# Schematics.net
KiCad netlist of a schematic drawn in Altium Designer
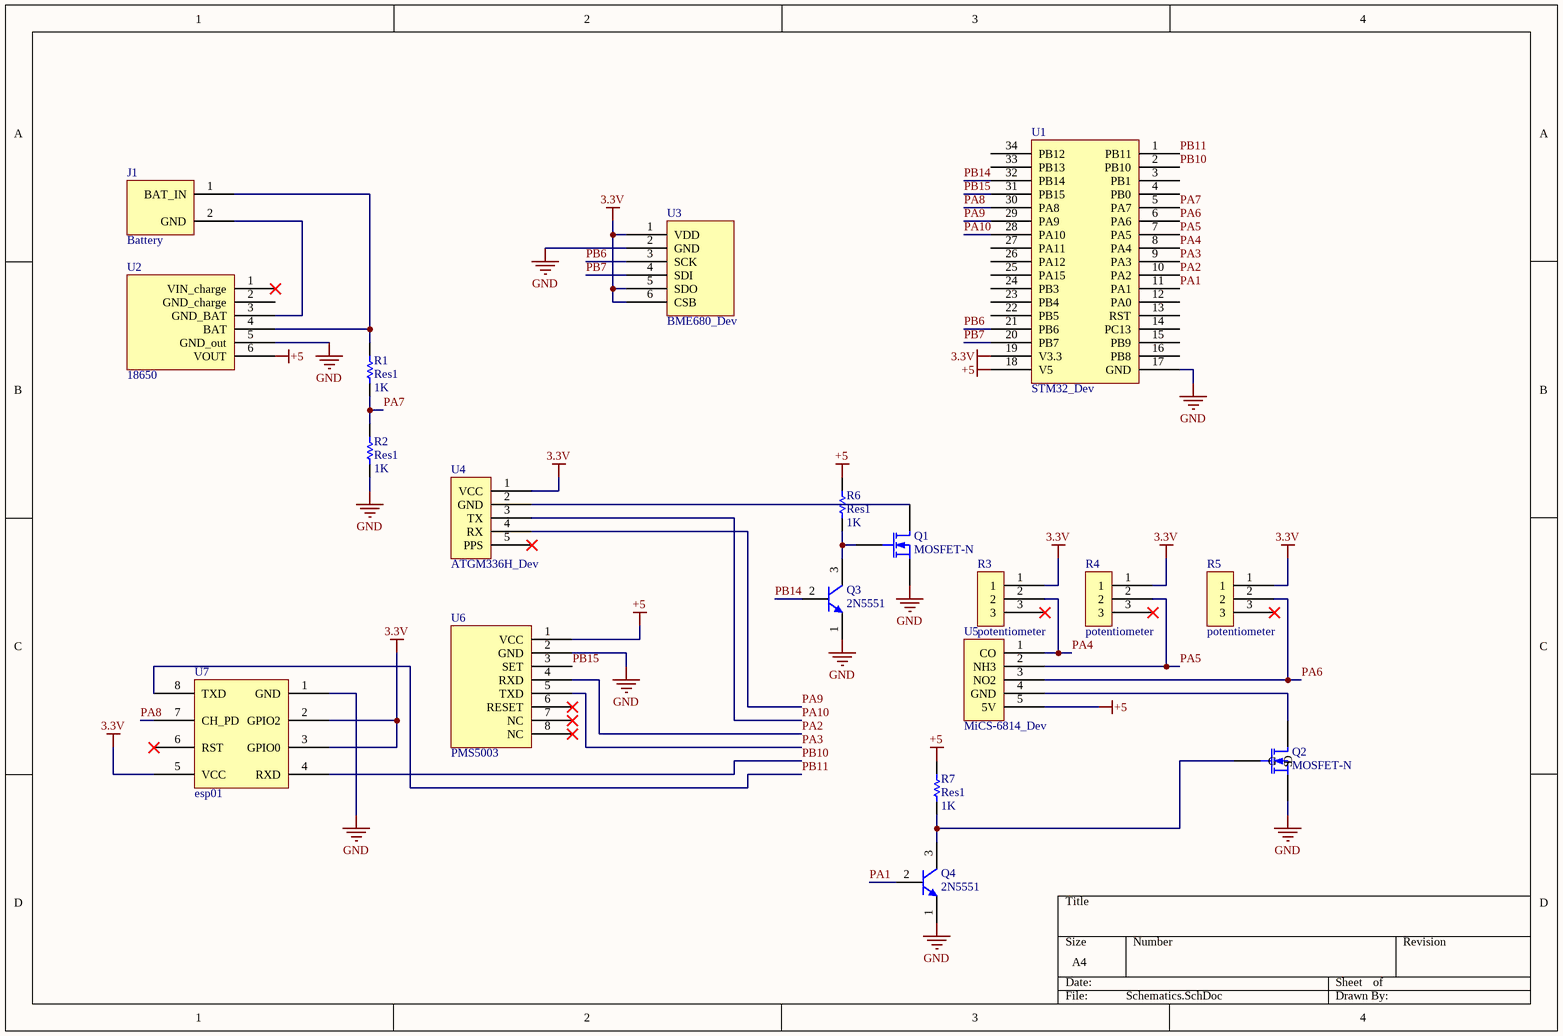
[diagram p0: Schematics.SchDoc]

(export (version "E")
  (design (tool "Eeschema 10.0.6"))
  (components
    (comp (ref "J1") (value "Battery") (footprint "Battery") (libsource (lib "SDLib") (part "Battery")))
    (comp (ref "Q1")
      (value "MOSFET-N")
      (footprint "TO-220-AB")
      (description "N-Channel MOSFET")
      (fields (field (name "PUBLISHER") "Altium Limited"))
      (libsource (lib "Miscellaneous Devices") (part "MOSFET-N"))
    )
    (comp (ref "Q2")
      (value "MOSFET-N")
      (footprint "TO-220-AB")
      (description "N-Channel MOSFET")
      (fields (field (name "PUBLISHER") "Altium Limited"))
      (libsource (lib "") (part "MOSFET-N_1"))
    )
    (comp (ref "Q3")
      (value "2N5551")
      (footprint "TO-92A")
      (description "NPN General Purpose Amplifier")
      (fields (field (name "PUBLISHER") "Altium Limited"))
      (libsource (lib "Miscellaneous Devices") (part "2N3904"))
    )
    (comp (ref "Q4")
      (value "2N5551")
      (footprint "TO-92A")
      (description "NPN General Purpose Amplifier")
      (fields (field (name "PUBLISHER") "Altium Limited"))
      (libsource (lib "Miscellaneous Devices") (part "2N3904"))
    )
    (comp (ref "R1")
      (value "Res1")
      (footprint "AXIAL-0.3")
      (description "Resistor")
      (fields (field (name "ALTIUM_VALUE") "1K") (field (name "PUBLISHER") "Altium Limited"))
      (libsource (lib "Miscellaneous Devices") (part "Res1"))
    )
    (comp (ref "R2")
      (value "Res1")
      (footprint "AXIAL-0.3")
      (description "Resistor")
      (fields (field (name "ALTIUM_VALUE") "1K") (field (name "PUBLISHER") "Altium Limited"))
      (libsource (lib "Miscellaneous Devices") (part "Res1"))
    )
    (comp (ref "R3")
      (value "potentiometer")
      (footprint "potentiometer")
      (libsource (lib "SDLib") (part "potentiometer"))
    )
    (comp (ref "R4")
      (value "potentiometer")
      (footprint "potentiometer")
      (libsource (lib "SDLib") (part "potentiometer"))
    )
    (comp (ref "R5")
      (value "potentiometer")
      (footprint "potentiometer")
      (libsource (lib "SDLib") (part "potentiometer"))
    )
    (comp (ref "R6")
      (value "Res1")
      (footprint "AXIAL-0.3")
      (description "Resistor")
      (fields (field (name "ALTIUM_VALUE") "1K") (field (name "PUBLISHER") "Altium Limited"))
      (libsource (lib "Miscellaneous Devices") (part "Res1"))
    )
    (comp (ref "R7")
      (value "Res1")
      (footprint "AXIAL-0.3")
      (description "Resistor")
      (fields (field (name "ALTIUM_VALUE") "1K") (field (name "PUBLISHER") "Altium Limited"))
      (libsource (lib "Miscellaneous Devices") (part "Res1"))
    )
    (comp (ref "U1") (value "STM32_Dev") (footprint "STM32_Dev") (libsource (lib "SDLib") (part "STM32_Dev")))
    (comp (ref "U2") (value "18650") (footprint "18650_Manage") (libsource (lib "SDLib") (part "18650")))
    (comp (ref "U3")
      (value "BME680_Dev")
      (footprint "BME680_Dev")
      (libsource (lib "SDLib") (part "BME680_Dev"))
    )
    (comp (ref "U4")
      (value "ATGM336H_Dev")
      (footprint "AGTM336H_Dev")
      (libsource (lib "SDLib") (part "ATGM336H_Dev"))
    )
    (comp (ref "U5")
      (value "MiCS-6814_Dev")
      (footprint "MiCS6814")
      (libsource (lib "SDLib") (part "MiCS-6814_Dev"))
    )
    (comp (ref "U6") (value "PMS5003") (footprint "PMS5003") (libsource (lib "SDLib") (part "PMS5003")))
    (comp (ref "U7") (value "esp01") (footprint "ESP01") (libsource (lib "SDLib") (part "esp01")))
  )
  (nets
    (net (code "1") (name "+5") (class "Default")
      (node (ref "R6") (pin "2") (pinfunction "2_2") (pintype "passive"))
      (node (ref "R7") (pin "2") (pinfunction "2_2") (pintype "passive"))
      (node (ref "U1") (pin "18") (pinfunction "V5_18") (pintype "passive"))
      (node (ref "U2") (pin "6") (pinfunction "VOUT_6") (pintype "passive"))
      (node (ref "U5") (pin "5") (pinfunction "5V_5") (pintype "passive"))
      (node (ref "U6") (pin "1") (pinfunction "VCC_1") (pintype "passive"))
    )
    (net (code "2") (name "/PA1") (class "Default")
      (node (ref "Q4") (pin "2") (pinfunction "B_2") (pintype "passive"))
      (node (ref "U1") (pin "11") (pinfunction "PA1_11") (pintype "passive"))
    )
    (net (code "3") (name "/PA2") (class "Default")
      (node (ref "U1") (pin "10") (pinfunction "PA2_10") (pintype "passive"))
      (node (ref "U6") (pin "4") (pinfunction "RXD_4") (pintype "passive"))
    )
    (net (code "4") (name "/PA3") (class "Default")
      (node (ref "U1") (pin "9") (pinfunction "PA3_9") (pintype "passive"))
      (node (ref "U6") (pin "5") (pinfunction "TXD_5") (pintype "passive"))
    )
    (net (code "5") (name "/PA4") (class "Default")
      (node (ref "R3") (pin "2") (pinfunction "2_2") (pintype "passive"))
      (node (ref "U1") (pin "8") (pinfunction "PA4_8") (pintype "passive"))
      (node (ref "U5") (pin "1") (pinfunction "CO_1") (pintype "passive"))
    )
    (net (code "6") (name "/PA5") (class "Default")
      (node (ref "R4") (pin "2") (pinfunction "2_2") (pintype "passive"))
      (node (ref "U1") (pin "7") (pinfunction "PA5_7") (pintype "passive"))
      (node (ref "U5") (pin "2") (pinfunction "NH3_2") (pintype "passive"))
    )
    (net (code "7") (name "/PA6") (class "Default")
      (node (ref "R5") (pin "2") (pinfunction "2_2") (pintype "passive"))
      (node (ref "U1") (pin "6") (pinfunction "PA6_6") (pintype "passive"))
      (node (ref "U5") (pin "3") (pinfunction "NO2_3") (pintype "passive"))
    )
    (net (code "8") (name "/PA7") (class "Default")
      (node (ref "R1") (pin "1") (pinfunction "1_1") (pintype "passive"))
      (node (ref "R2") (pin "2") (pinfunction "2_2") (pintype "passive"))
      (node (ref "U1") (pin "5") (pinfunction "PA7_5") (pintype "passive"))
    )
    (net (code "9") (name "/PA8") (class "Default")
      (node (ref "U1") (pin "30") (pinfunction "PA8_30") (pintype "passive"))
      (node (ref "U7") (pin "7") (pinfunction "CH_PD_7") (pintype "passive"))
    )
    (net (code "10") (name "/PA9") (class "Default")
      (node (ref "U1") (pin "29") (pinfunction "PA9_29") (pintype "passive"))
      (node (ref "U4") (pin "4") (pinfunction "RX_4") (pintype "passive"))
    )
    (net (code "11") (name "/PA10") (class "Default")
      (node (ref "U1") (pin "28") (pinfunction "PA10_28") (pintype "passive"))
      (node (ref "U4") (pin "3") (pinfunction "TX_3") (pintype "passive"))
    )
    (net (code "12") (name "/PB6") (class "Default")
      (node (ref "U1") (pin "21") (pinfunction "PB6_21") (pintype "passive"))
      (node (ref "U3") (pin "3") (pinfunction "SCK_3") (pintype "passive"))
    )
    (net (code "13") (name "/PB7") (class "Default")
      (node (ref "U1") (pin "20") (pinfunction "PB7_20") (pintype "passive"))
      (node (ref "U3") (pin "4") (pinfunction "SDI_4") (pintype "passive"))
    )
    (net (code "14") (name "/PB10") (class "Default")
      (node (ref "U1") (pin "2") (pinfunction "PB10_2") (pintype "passive"))
      (node (ref "U7") (pin "4") (pinfunction "RXD_4") (pintype "passive"))
    )
    (net (code "15") (name "/PB11") (class "Default")
      (node (ref "U1") (pin "1") (pinfunction "PB11_1") (pintype "passive"))
      (node (ref "U7") (pin "8") (pinfunction "TXD_8") (pintype "passive"))
    )
    (net (code "16") (name "/PB14") (class "Default")
      (node (ref "Q3") (pin "2") (pinfunction "B_2") (pintype "passive"))
      (node (ref "U1") (pin "32") (pinfunction "PB14_32") (pintype "passive"))
    )
    (net (code "17") (name "/PB15") (class "Default")
      (node (ref "U1") (pin "31") (pinfunction "PB15_31") (pintype "passive"))
      (node (ref "U6") (pin "3") (pinfunction "SET_3") (pintype "passive"))
    )
    (net (code "18") (name "3.3V") (class "Default")
      (node (ref "R3") (pin "1") (pinfunction "1_1") (pintype "passive"))
      (node (ref "R4") (pin "1") (pinfunction "1_1") (pintype "passive"))
      (node (ref "R5") (pin "1") (pinfunction "1_1") (pintype "passive"))
      (node (ref "U1") (pin "19") (pinfunction "V3.3_19") (pintype "passive"))
      (node (ref "U3") (pin "1") (pinfunction "VDD_1") (pintype "passive"))
      (node (ref "U3") (pin "5") (pinfunction "SDO_5") (pintype "passive"))
      (node (ref "U3") (pin "6") (pinfunction "CSB_6") (pintype "passive"))
      (node (ref "U4") (pin "1") (pinfunction "VCC_1") (pintype "passive"))
      (node (ref "U7") (pin "2") (pinfunction "GPIO2_2") (pintype "passive"))
      (node (ref "U7") (pin "3") (pinfunction "GPIO0_3") (pintype "passive"))
      (node (ref "U7") (pin "5") (pinfunction "VCC_5") (pintype "passive"))
    )
    (net (code "19") (name "GND") (class "Default")
      (node (ref "Q1") (pin "3") (pinfunction "S_3") (pintype "passive"))
      (node (ref "Q2") (pin "3") (pinfunction "S_3") (pintype "passive"))
      (node (ref "Q3") (pin "1") (pinfunction "E_1") (pintype "passive"))
      (node (ref "Q4") (pin "1") (pinfunction "E_1") (pintype "passive"))
      (node (ref "R2") (pin "1") (pinfunction "1_1") (pintype "passive"))
      (node (ref "U1") (pin "17") (pinfunction "GND_17") (pintype "passive"))
      (node (ref "U2") (pin "5") (pinfunction "GND_out_5") (pintype "passive"))
      (node (ref "U3") (pin "2") (pinfunction "GND_2") (pintype "passive"))
      (node (ref "U6") (pin "2") (pinfunction "GND_2") (pintype "passive"))
      (node (ref "U7") (pin "1") (pinfunction "GND_1") (pintype "passive"))
    )
    (net (code "20") (name "Net-(J1-BAT_IN)") (class "Default")
      (node (ref "J1") (pin "1") (pinfunction "BAT_IN_1") (pintype "passive"))
      (node (ref "R1") (pin "2") (pinfunction "2_2") (pintype "passive"))
      (node (ref "U2") (pin "4") (pinfunction "BAT_4") (pintype "passive"))
    )
    (net (code "21") (name "Net-(J1-GND)") (class "Default")
      (node (ref "J1") (pin "2") (pinfunction "GND_2") (pintype "passive"))
      (node (ref "U2") (pin "3") (pinfunction "GND_BAT_3") (pintype "passive"))
    )
    (net (code "22") (name "Net-(Q1-D)") (class "Default")
      (node (ref "Q1") (pin "2") (pinfunction "D_2") (pintype "passive"))
      (node (ref "U4") (pin "2") (pinfunction "GND_2") (pintype "passive"))
    )
    (net (code "23") (name "Net-(Q1-G)") (class "Default")
      (node (ref "Q1") (pin "1") (pinfunction "G_1") (pintype "passive"))
      (node (ref "Q3") (pin "3") (pinfunction "C_3") (pintype "passive"))
      (node (ref "R6") (pin "1") (pinfunction "1_1") (pintype "passive"))
    )
    (net (code "24") (name "Net-(Q2-D)") (class "Default")
      (node (ref "Q2") (pin "2") (pinfunction "D_2") (pintype "passive"))
      (node (ref "U5") (pin "4") (pinfunction "GND_4") (pintype "passive"))
    )
    (net (code "25") (name "Net-(Q2-G)") (class "Default")
      (node (ref "Q2") (pin "1") (pinfunction "G_1") (pintype "passive"))
      (node (ref "Q4") (pin "3") (pinfunction "C_3") (pintype "passive"))
      (node (ref "R7") (pin "1") (pinfunction "1_1") (pintype "passive"))
    )
    (net (code "26") (name "unconnected-(R3-Pad3)") (class "Default")
      (node (ref "R3") (pin "3") (pinfunction "3_3") (pintype "passive+no_connect"))
    )
    (net (code "27") (name "unconnected-(R4-Pad3)") (class "Default")
      (node (ref "R4") (pin "3") (pinfunction "3_3") (pintype "passive+no_connect"))
    )
    (net (code "28") (name "unconnected-(R5-Pad3)") (class "Default")
      (node (ref "R5") (pin "3") (pinfunction "3_3") (pintype "passive+no_connect"))
    )
    (net (code "29") (name "unconnected-(U1-PA0-Pad12)") (class "Default")
      (node (ref "U1") (pin "12") (pinfunction "PA0_12") (pintype "passive"))
    )
    (net (code "30") (name "unconnected-(U1-PA11-Pad27)") (class "Default")
      (node (ref "U1") (pin "27") (pinfunction "PA11_27") (pintype "passive"))
    )
    (net (code "31") (name "unconnected-(U1-PA12-Pad26)") (class "Default")
      (node (ref "U1") (pin "26") (pinfunction "PA12_26") (pintype "passive"))
    )
    (net (code "32") (name "unconnected-(U1-PA15-Pad25)") (class "Default")
      (node (ref "U1") (pin "25") (pinfunction "PA15_25") (pintype "passive"))
    )
    (net (code "33") (name "unconnected-(U1-PB0-Pad4)") (class "Default")
      (node (ref "U1") (pin "4") (pinfunction "PB0_4") (pintype "passive"))
    )
    (net (code "34") (name "unconnected-(U1-PB1-Pad3)") (class "Default")
      (node (ref "U1") (pin "3") (pinfunction "PB1_3") (pintype "passive"))
    )
    (net (code "35") (name "unconnected-(U1-PB3-Pad24)") (class "Default")
      (node (ref "U1") (pin "24") (pinfunction "PB3_24") (pintype "passive"))
    )
    (net (code "36") (name "unconnected-(U1-PB4-Pad23)") (class "Default")
      (node (ref "U1") (pin "23") (pinfunction "PB4_23") (pintype "passive"))
    )
    (net (code "37") (name "unconnected-(U1-PB5-Pad22)") (class "Default")
      (node (ref "U1") (pin "22") (pinfunction "PB5_22") (pintype "passive"))
    )
    (net (code "38") (name "unconnected-(U1-PB8-Pad16)") (class "Default")
      (node (ref "U1") (pin "16") (pinfunction "PB8_16") (pintype "passive"))
    )
    (net (code "39") (name "unconnected-(U1-PB9-Pad15)") (class "Default")
      (node (ref "U1") (pin "15") (pinfunction "PB9_15") (pintype "passive"))
    )
    (net (code "40") (name "unconnected-(U1-PB12-Pad34)") (class "Default")
      (node (ref "U1") (pin "34") (pinfunction "PB12_34") (pintype "passive"))
    )
    (net (code "41") (name "unconnected-(U1-PB13-Pad33)") (class "Default")
      (node (ref "U1") (pin "33") (pinfunction "PB13_33") (pintype "passive"))
    )
    (net (code "42") (name "unconnected-(U1-PC13-Pad14)") (class "Default")
      (node (ref "U1") (pin "14") (pinfunction "PC13_14") (pintype "passive"))
    )
    (net (code "43") (name "unconnected-(U1-RST-Pad13)") (class "Default")
      (node (ref "U1") (pin "13") (pinfunction "RST_13") (pintype "passive"))
    )
    (net (code "44") (name "unconnected-(U2-GND_charge-Pad2)") (class "Default")
      (node (ref "U2") (pin "2") (pinfunction "GND_charge_2") (pintype "passive"))
    )
    (net (code "45") (name "unconnected-(U2-VIN_charge-Pad1)") (class "Default")
      (node (ref "U2") (pin "1") (pinfunction "VIN_charge_1") (pintype "passive+no_connect"))
    )
    (net (code "46") (name "unconnected-(U4-PPS-Pad5)") (class "Default")
      (node (ref "U4") (pin "5") (pinfunction "PPS_5") (pintype "passive+no_connect"))
    )
    (net (code "47") (name "unconnected-(U6-NC-Pad7)") (class "Default")
      (node (ref "U6") (pin "7") (pinfunction "NC_7") (pintype "passive+no_connect"))
    )
    (net (code "48") (name "unconnected-(U6-NC-Pad8)") (class "Default")
      (node (ref "U6") (pin "8") (pinfunction "NC_8") (pintype "passive+no_connect"))
    )
    (net (code "49") (name "unconnected-(U6-RESET-Pad6)") (class "Default")
      (node (ref "U6") (pin "6") (pinfunction "RESET_6") (pintype "passive+no_connect"))
    )
    (net (code "50") (name "unconnected-(U7-RST-Pad6)") (class "Default")
      (node (ref "U7") (pin "6") (pinfunction "RST_6") (pintype "passive+no_connect"))
    )
  )
)
